# IotaWatt5_0.net
KiCad netlist of a schematic drawn in EAGLE
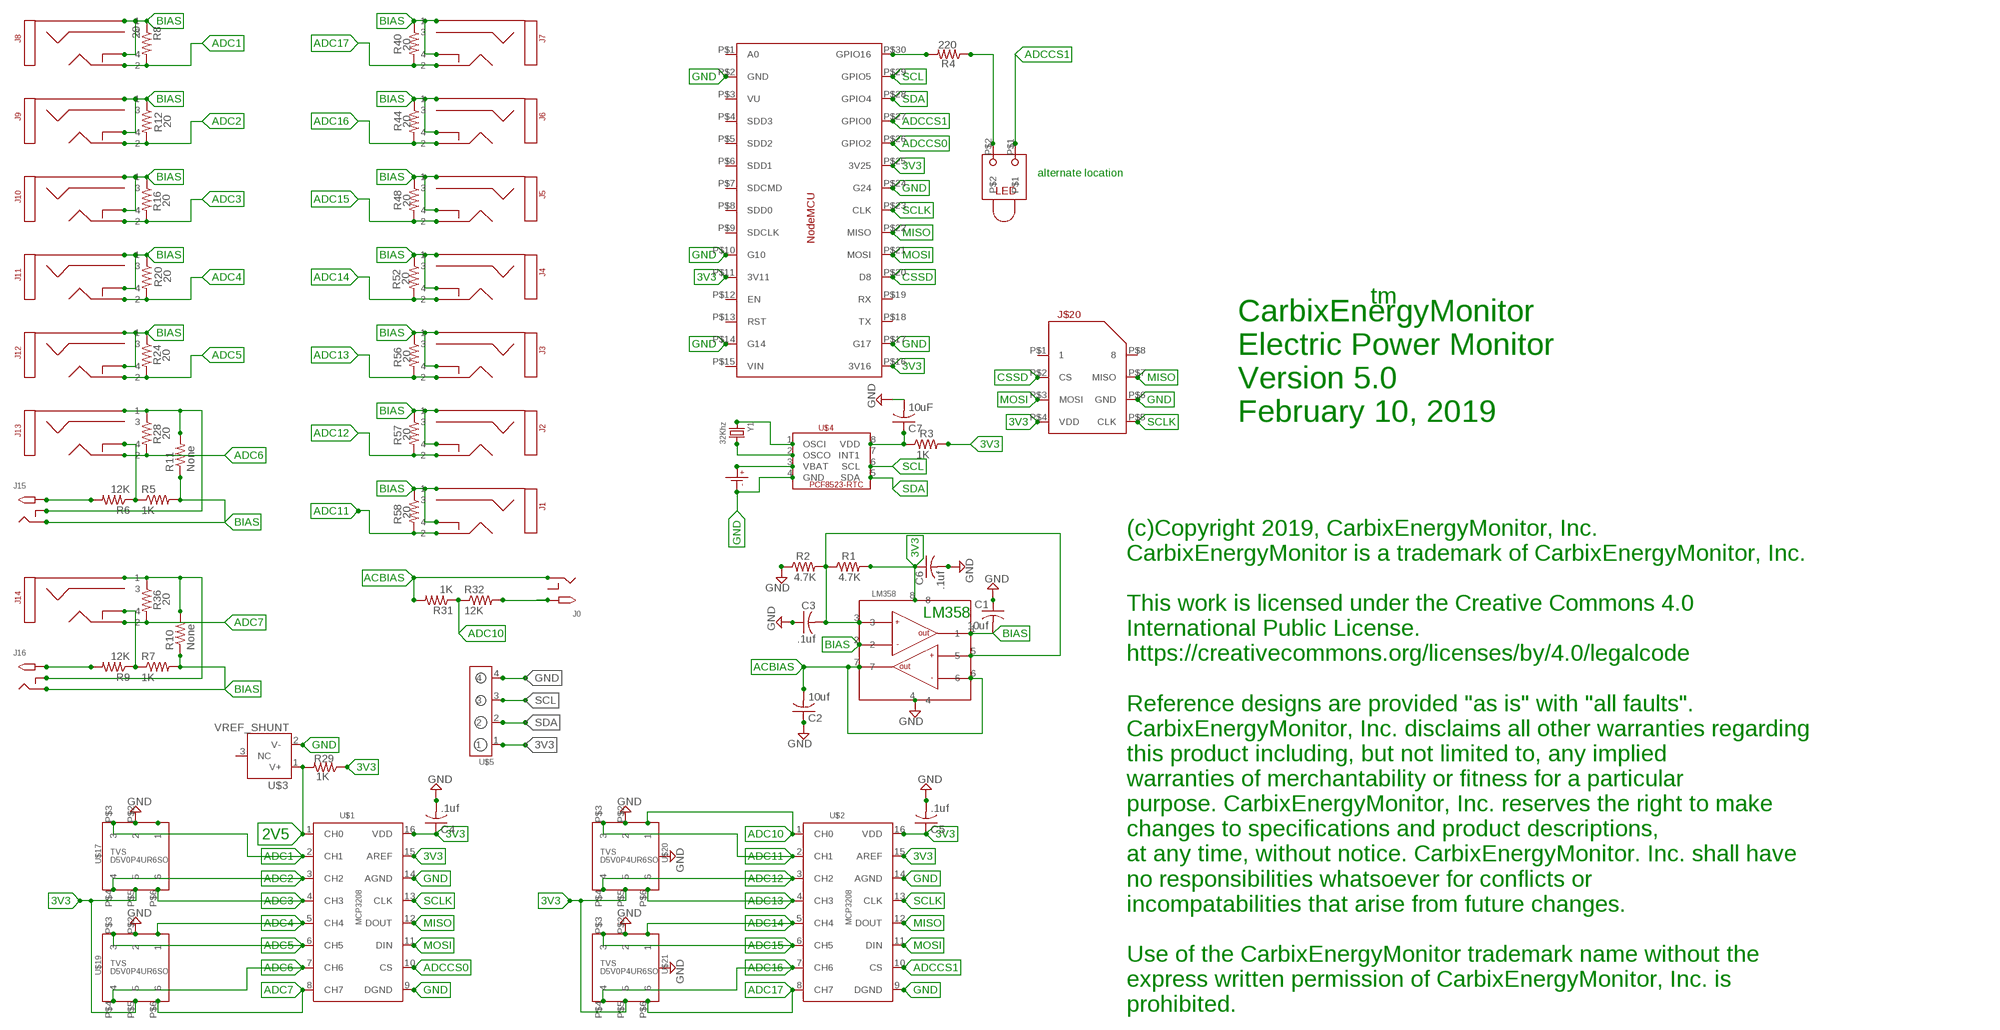
[diagram p0: schematic, sheet 1]

(export (version "E")
  (design (tool "Eeschema 10.0.6"))
  (components
    (comp (ref "C1")
      (value "10uf")
      (footprint "eagle-import:C0805")
      (libsource (lib "eagle-import") (part "C-USC0805"))
    )
    (comp (ref "C2")
      (value "10uf")
      (footprint "eagle-import:C0805")
      (libsource (lib "eagle-import") (part "C-USC0805"))
    )
    (comp (ref "C3")
      (value ".1uf")
      (footprint "eagle-import:C0805")
      (libsource (lib "eagle-import") (part "C-USC0805"))
    )
    (comp (ref "C4")
      (value ".1uf")
      (footprint "eagle-import:C0805")
      (libsource (lib "eagle-import") (part "C-USC0805"))
    )
    (comp (ref "C5")
      (value ".1uf")
      (footprint "eagle-import:C0805")
      (libsource (lib "eagle-import") (part "C-USC0805"))
    )
    (comp (ref "C6")
      (value ".1uf")
      (footprint "eagle-import:C0805")
      (libsource (lib "eagle-import") (part "C-USC0805"))
    )
    (comp (ref "C7")
      (value "10uF")
      (footprint "eagle-import:C0805")
      (libsource (lib "eagle-import") (part "C-USC0805"))
    )
    (comp (ref "J$20")
      (value "MICROSD_PUSH/PULL")
      (footprint "eagle-import:MICROSD")
      (libsource (lib "eagle-import") (part "MICROSD_PUSH/PULL"))
    )
    (comp (ref "J0")
      (value "2.1MMJACKSMT")
      (footprint "eagle-import:DCJACK_2MM_SMT")
      (libsource (lib "eagle-import") (part "2.1MMJACKSMT"))
    )
    (comp (ref "J1")
      (value "STEREO_SMD")
      (footprint "eagle-import:STEREO_SMT")
      (libsource (lib "eagle-import") (part "STEREO_SMD"))
    )
    (comp (ref "J2")
      (value "STEREO_SMD")
      (footprint "eagle-import:STEREO_SMT")
      (libsource (lib "eagle-import") (part "STEREO_SMD"))
    )
    (comp (ref "J3")
      (value "STEREO_SMD")
      (footprint "eagle-import:STEREO_SMT")
      (libsource (lib "eagle-import") (part "STEREO_SMD"))
    )
    (comp (ref "J4")
      (value "STEREO_SMD")
      (footprint "eagle-import:STEREO_SMT")
      (libsource (lib "eagle-import") (part "STEREO_SMD"))
    )
    (comp (ref "J5")
      (value "STEREO_SMD")
      (footprint "eagle-import:STEREO_SMT")
      (libsource (lib "eagle-import") (part "STEREO_SMD"))
    )
    (comp (ref "J6")
      (value "STEREO_SMD")
      (footprint "eagle-import:STEREO_SMT")
      (libsource (lib "eagle-import") (part "STEREO_SMD"))
    )
    (comp (ref "J7")
      (value "STEREO_SMD")
      (footprint "eagle-import:STEREO_SMT")
      (libsource (lib "eagle-import") (part "STEREO_SMD"))
    )
    (comp (ref "J8")
      (value "STEREO_SMD")
      (footprint "eagle-import:STEREO_SMT")
      (libsource (lib "eagle-import") (part "STEREO_SMD"))
    )
    (comp (ref "J9")
      (value "STEREO_SMD")
      (footprint "eagle-import:STEREO_SMT")
      (libsource (lib "eagle-import") (part "STEREO_SMD"))
    )
    (comp (ref "J10")
      (value "STEREO_SMD")
      (footprint "eagle-import:STEREO_SMT")
      (libsource (lib "eagle-import") (part "STEREO_SMD"))
    )
    (comp (ref "J11")
      (value "STEREO_SMD")
      (footprint "eagle-import:STEREO_SMT")
      (libsource (lib "eagle-import") (part "STEREO_SMD"))
    )
    (comp (ref "J12")
      (value "STEREO_SMD")
      (footprint "eagle-import:STEREO_SMT")
      (libsource (lib "eagle-import") (part "STEREO_SMD"))
    )
    (comp (ref "J13")
      (value "STEREO_SMD")
      (footprint "eagle-import:STEREO_SMT")
      (libsource (lib "eagle-import") (part "STEREO_SMD"))
    )
    (comp (ref "J14")
      (value "STEREO_SMD")
      (footprint "eagle-import:STEREO_SMT")
      (libsource (lib "eagle-import") (part "STEREO_SMD"))
    )
    (comp (ref "J15")
      (value "2.1MMJACKSMT")
      (footprint "eagle-import:DCJACK_2MM_SMT")
      (libsource (lib "eagle-import") (part "2.1MMJACKSMT"))
    )
    (comp (ref "J16")
      (value "2.1MMJACKSMT")
      (footprint "eagle-import:DCJACK_2MM_SMT")
      (libsource (lib "eagle-import") (part "2.1MMJACKSMT"))
    )
    (comp (ref "R1")
      (value "4.7K")
      (footprint "eagle-import:R0805")
      (libsource (lib "eagle-import") (part "R-US_R0805"))
    )
    (comp (ref "R2")
      (value "4.7K")
      (footprint "eagle-import:R0805")
      (libsource (lib "eagle-import") (part "R-US_R0805"))
    )
    (comp (ref "R3")
      (value "1K")
      (footprint "eagle-import:R0805")
      (libsource (lib "eagle-import") (part "R-US_R0805"))
    )
    (comp (ref "R4")
      (value "220")
      (footprint "eagle-import:R0805")
      (libsource (lib "eagle-import") (part "R-US_R0805"))
    )
    (comp (ref "R5")
      (value "1K")
      (footprint "eagle-import:R0805")
      (libsource (lib "eagle-import") (part "R-US_R0805"))
    )
    (comp (ref "R6")
      (value "12K")
      (footprint "eagle-import:R0805")
      (libsource (lib "eagle-import") (part "R-US_R0805"))
    )
    (comp (ref "R7")
      (value "1K")
      (footprint "eagle-import:R0805")
      (libsource (lib "eagle-import") (part "R-US_R0805"))
    )
    (comp (ref "R8")
      (value "20")
      (footprint "eagle-import:R0805")
      (libsource (lib "eagle-import") (part "R-US_R0805"))
    )
    (comp (ref "R9")
      (value "12K")
      (footprint "eagle-import:R0805")
      (libsource (lib "eagle-import") (part "R-US_R0805"))
    )
    (comp (ref "R10")
      (value "None")
      (footprint "eagle-import:R0805")
      (libsource (lib "eagle-import") (part "R-US_R0805"))
    )
    (comp (ref "R11")
      (value "None")
      (footprint "eagle-import:R0805")
      (libsource (lib "eagle-import") (part "R-US_R0805"))
    )
    (comp (ref "R12")
      (value "20")
      (footprint "eagle-import:R0805")
      (libsource (lib "eagle-import") (part "R-US_R0805"))
    )
    (comp (ref "R16")
      (value "20")
      (footprint "eagle-import:R0805")
      (libsource (lib "eagle-import") (part "R-US_R0805"))
    )
    (comp (ref "R20")
      (value "20")
      (footprint "eagle-import:R0805")
      (libsource (lib "eagle-import") (part "R-US_R0805"))
    )
    (comp (ref "R24")
      (value "20")
      (footprint "eagle-import:R0805")
      (libsource (lib "eagle-import") (part "R-US_R0805"))
    )
    (comp (ref "R28")
      (value "20")
      (footprint "eagle-import:R0805")
      (libsource (lib "eagle-import") (part "R-US_R0805"))
    )
    (comp (ref "R29")
      (value "1K")
      (footprint "eagle-import:R0805")
      (libsource (lib "eagle-import") (part "R-US_R0805"))
    )
    (comp (ref "R31")
      (value "1K")
      (footprint "eagle-import:R0805")
      (libsource (lib "eagle-import") (part "R-US_R0805"))
    )
    (comp (ref "R32")
      (value "12K")
      (footprint "eagle-import:R0805")
      (libsource (lib "eagle-import") (part "R-US_R0805"))
    )
    (comp (ref "R36")
      (value "20")
      (footprint "eagle-import:R0805")
      (libsource (lib "eagle-import") (part "R-US_R0805"))
    )
    (comp (ref "R40")
      (value "20")
      (footprint "eagle-import:R0805")
      (libsource (lib "eagle-import") (part "R-US_R0805"))
    )
    (comp (ref "R44")
      (value "20")
      (footprint "eagle-import:R0805")
      (libsource (lib "eagle-import") (part "R-US_R0805"))
    )
    (comp (ref "R48")
      (value "20")
      (footprint "eagle-import:R0805")
      (libsource (lib "eagle-import") (part "R-US_R0805"))
    )
    (comp (ref "R52")
      (value "20")
      (footprint "eagle-import:R0805")
      (libsource (lib "eagle-import") (part "R-US_R0805"))
    )
    (comp (ref "R56")
      (value "20")
      (footprint "eagle-import:R0805")
      (libsource (lib "eagle-import") (part "R-US_R0805"))
    )
    (comp (ref "R57")
      (value "20")
      (footprint "eagle-import:R0805")
      (libsource (lib "eagle-import") (part "R-US_R0805"))
    )
    (comp (ref "R58")
      (value "20")
      (footprint "eagle-import:R0805")
      (libsource (lib "eagle-import") (part "R-US_R0805"))
    )
    (comp (ref "U$1")
      (value "MCP3208")
      (footprint "eagle-import:SOIC_16")
      (libsource (lib "eagle-import") (part "MCP3208"))
    )
    (comp (ref "U$2")
      (value "MCP3208")
      (footprint "eagle-import:SOIC_16")
      (libsource (lib "eagle-import") (part "MCP3208"))
    )
    (comp (ref "U$3")
      (value "VREF_SHUNT")
      (footprint "eagle-import:SOT23_3")
      (libsource (lib "eagle-import") (part "VREF_SHUNT"))
    )
    (comp (ref "U$4")
      (value "PCF8523_RTC")
      (footprint "eagle-import:SOIC_8")
      (libsource (lib "eagle-import") (part "PCF8523_RTC"))
    )
    (comp (ref "U$5")
      (value "HEADER_1X4")
      (footprint "eagle-import:HEADER_1X4")
      (libsource (lib "eagle-import") (part "HEADER_1X4"))
    )
    (comp (ref "U$16")
      (value "NODEMCU")
      (footprint "eagle-import:NODEMCU")
      (libsource (lib "eagle-import") (part "NODEMCU"))
    )
    (comp (ref "U$17")
      (value "TVS_4CHAN_ARRAYSC-74")
      (footprint "eagle-import:SC-74")
      (libsource (lib "eagle-import") (part "TVS_4CHAN_ARRAYSC-74"))
    )
    (comp (ref "U$18")
      (value "CR1220SMD")
      (footprint "eagle-import:CR1220SMD")
      (libsource (lib "eagle-import") (part "CR1220SMD"))
    )
    (comp (ref "U$19")
      (value "TVS_4CHAN_ARRAYSC-74")
      (footprint "eagle-import:SC-74")
      (libsource (lib "eagle-import") (part "TVS_4CHAN_ARRAYSC-74"))
    )
    (comp (ref "U$20")
      (value "TVS_4CHAN_ARRAYSC-74")
      (footprint "eagle-import:SC-74")
      (libsource (lib "eagle-import") (part "TVS_4CHAN_ARRAYSC-74"))
    )
    (comp (ref "U$21")
      (value "TVS_4CHAN_ARRAYSC-74")
      (footprint "eagle-import:SC-74")
      (libsource (lib "eagle-import") (part "TVS_4CHAN_ARRAYSC-74"))
    )
    (comp (ref "U$22")
      (value "LM358_DUAL_OP-AMP")
      (footprint "eagle-import:SOIC_8")
      (libsource (lib "eagle-import") (part "LM358_DUAL_OP-AMP"))
    )
    (comp (ref "U$23")
      (value "LED_RT_TRH")
      (footprint "eagle-import:LED_TH_RT")
      (libsource (lib "eagle-import") (part "LED_RT_TRH"))
    )
    (comp (ref "Y1")
      (value "32Khz")
      (footprint "eagle-import:CRYSTAL_8X3.8")
      (libsource (lib "eagle-import") (part "CRYSTAL8X3.8SMT"))
    )
  )
  (nets
    (net (code "1") (name "2V5") (class "Default")
      (node (ref "R29") (pin "2") (pinfunction "2_2") (pintype "passive"))
      (node (ref "U$1") (pin "1") (pinfunction "CH0_1") (pintype "input"))
      (node (ref "U$3") (pin "1") (pinfunction "V+_1") (pintype "bidirectional"))
    )
    (net (code "2") (name "3V3") (class "Default")
      (node (ref "C4") (pin "1") (pinfunction "1_1") (pintype "passive"))
      (node (ref "C5") (pin "1") (pinfunction "1_1") (pintype "passive"))
      (node (ref "C6") (pin "1") (pinfunction "1_1") (pintype "passive"))
      (node (ref "J$20") (pin "P$4") (pinfunction "VDD_P$4") (pintype "bidirectional"))
      (node (ref "R1") (pin "2") (pinfunction "2_2") (pintype "passive"))
      (node (ref "R29") (pin "1") (pinfunction "1_1") (pintype "passive"))
      (node (ref "R3") (pin "2") (pinfunction "2_2") (pintype "passive"))
      (node (ref "U$1") (pin "15") (pinfunction "AREF_15") (pintype "input"))
      (node (ref "U$1") (pin "16") (pinfunction "VDD_16") (pintype "bidirectional"))
      (node (ref "U$16") (pin "P$11") (pinfunction "3V11_P$11") (pintype "bidirectional"))
      (node (ref "U$16") (pin "P$16") (pinfunction "3V16_P$16") (pintype "bidirectional"))
      (node (ref "U$16") (pin "P$25") (pinfunction "3V25_P$25") (pintype "bidirectional"))
      (node (ref "U$17") (pin "P$5") (pinfunction "5_P$5") (pintype "bidirectional"))
      (node (ref "U$19") (pin "P$5") (pinfunction "5_P$5") (pintype "bidirectional"))
      (node (ref "U$2") (pin "15") (pinfunction "AREF_15") (pintype "input"))
      (node (ref "U$2") (pin "16") (pinfunction "VDD_16") (pintype "bidirectional"))
      (node (ref "U$20") (pin "P$5") (pinfunction "5_P$5") (pintype "bidirectional"))
      (node (ref "U$21") (pin "P$5") (pinfunction "5_P$5") (pintype "bidirectional"))
      (node (ref "U$22") (pin "8") (pinfunction "8_8") (pintype "bidirectional"))
      (node (ref "U$5") (pin "1") (pinfunction "1_1") (pintype "bidirectional"))
    )
    (net (code "3") (name "ACBIAS") (class "Default")
      (node (ref "C2") (pin "2") (pinfunction "2_2") (pintype "passive"))
      (node (ref "J0") (pin "GND") (pinfunction "RING_GND") (pintype "bidirectional"))
      (node (ref "R31") (pin "2") (pinfunction "2_2") (pintype "passive"))
      (node (ref "U$22") (pin "6") (pinfunction "6_6") (pintype "bidirectional"))
      (node (ref "U$22") (pin "7") (pinfunction "7_7") (pintype "bidirectional"))
    )
    (net (code "4") (name "ADC1") (class "Default")
      (node (ref "J8") (pin "P$2") (pinfunction "2_P$2") (pintype "bidirectional"))
      (node (ref "R8") (pin "2") (pinfunction "2_2") (pintype "passive"))
      (node (ref "U$1") (pin "2") (pinfunction "CH1_2") (pintype "input"))
      (node (ref "U$17") (pin "P$3") (pinfunction "3_P$3") (pintype "bidirectional"))
    )
    (net (code "5") (name "ADC2") (class "Default")
      (node (ref "J9") (pin "P$2") (pinfunction "2_P$2") (pintype "bidirectional"))
      (node (ref "R12") (pin "2") (pinfunction "2_2") (pintype "passive"))
      (node (ref "U$1") (pin "3") (pinfunction "CH2_3") (pintype "input"))
      (node (ref "U$17") (pin "P$4") (pinfunction "4_P$4") (pintype "bidirectional"))
    )
    (net (code "6") (name "ADC3") (class "Default")
      (node (ref "J10") (pin "P$2") (pinfunction "2_P$2") (pintype "bidirectional"))
      (node (ref "R16") (pin "2") (pinfunction "2_2") (pintype "passive"))
      (node (ref "U$1") (pin "4") (pinfunction "CH3_4") (pintype "input"))
      (node (ref "U$17") (pin "P$6") (pinfunction "6_P$6") (pintype "bidirectional"))
    )
    (net (code "7") (name "ADC4") (class "Default")
      (node (ref "J11") (pin "P$2") (pinfunction "2_P$2") (pintype "bidirectional"))
      (node (ref "R20") (pin "2") (pinfunction "2_2") (pintype "passive"))
      (node (ref "U$1") (pin "5") (pinfunction "CH4_5") (pintype "bidirectional"))
      (node (ref "U$19") (pin "P$1") (pinfunction "1_P$1") (pintype "bidirectional"))
    )
    (net (code "8") (name "ADC5") (class "Default")
      (node (ref "J12") (pin "P$2") (pinfunction "2_P$2") (pintype "bidirectional"))
      (node (ref "R24") (pin "2") (pinfunction "2_2") (pintype "passive"))
      (node (ref "U$1") (pin "6") (pinfunction "CH5_6") (pintype "bidirectional"))
      (node (ref "U$19") (pin "P$3") (pinfunction "3_P$3") (pintype "bidirectional"))
    )
    (net (code "9") (name "ADC6") (class "Default")
      (node (ref "J13") (pin "P$2") (pinfunction "2_P$2") (pintype "bidirectional"))
      (node (ref "R28") (pin "2") (pinfunction "2_2") (pintype "passive"))
      (node (ref "U$1") (pin "7") (pinfunction "CH6_7") (pintype "input"))
      (node (ref "U$19") (pin "P$4") (pinfunction "4_P$4") (pintype "bidirectional"))
    )
    (net (code "10") (name "ADC7") (class "Default")
      (node (ref "J14") (pin "P$2") (pinfunction "2_P$2") (pintype "bidirectional"))
      (node (ref "R36") (pin "2") (pinfunction "2_2") (pintype "passive"))
      (node (ref "U$1") (pin "8") (pinfunction "CH7_8") (pintype "bidirectional"))
      (node (ref "U$19") (pin "P$6") (pinfunction "6_P$6") (pintype "bidirectional"))
    )
    (net (code "11") (name "ADC10") (class "Default")
      (node (ref "R31") (pin "1") (pinfunction "1_1") (pintype "passive"))
      (node (ref "R32") (pin "1") (pinfunction "1_1") (pintype "passive"))
      (node (ref "U$2") (pin "1") (pinfunction "CH0_1") (pintype "input"))
      (node (ref "U$20") (pin "P$1") (pinfunction "1_P$1") (pintype "bidirectional"))
    )
    (net (code "12") (name "ADC11") (class "Default")
      (node (ref "J1") (pin "P$2") (pinfunction "2_P$2") (pintype "bidirectional"))
      (node (ref "R58") (pin "2") (pinfunction "2_2") (pintype "passive"))
      (node (ref "U$2") (pin "2") (pinfunction "CH1_2") (pintype "input"))
      (node (ref "U$20") (pin "P$3") (pinfunction "3_P$3") (pintype "bidirectional"))
    )
    (net (code "13") (name "ADC12") (class "Default")
      (node (ref "J2") (pin "P$2") (pinfunction "2_P$2") (pintype "bidirectional"))
      (node (ref "R57") (pin "2") (pinfunction "2_2") (pintype "passive"))
      (node (ref "U$2") (pin "3") (pinfunction "CH2_3") (pintype "input"))
      (node (ref "U$20") (pin "P$4") (pinfunction "4_P$4") (pintype "bidirectional"))
    )
    (net (code "14") (name "ADC13") (class "Default")
      (node (ref "J3") (pin "P$2") (pinfunction "2_P$2") (pintype "bidirectional"))
      (node (ref "R56") (pin "2") (pinfunction "2_2") (pintype "passive"))
      (node (ref "U$2") (pin "4") (pinfunction "CH3_4") (pintype "input"))
      (node (ref "U$20") (pin "P$6") (pinfunction "6_P$6") (pintype "bidirectional"))
    )
    (net (code "15") (name "ADC14") (class "Default")
      (node (ref "J4") (pin "P$2") (pinfunction "2_P$2") (pintype "bidirectional"))
      (node (ref "R52") (pin "2") (pinfunction "2_2") (pintype "passive"))
      (node (ref "U$2") (pin "5") (pinfunction "CH4_5") (pintype "bidirectional"))
      (node (ref "U$21") (pin "P$1") (pinfunction "1_P$1") (pintype "bidirectional"))
    )
    (net (code "16") (name "ADC15") (class "Default")
      (node (ref "J5") (pin "P$2") (pinfunction "2_P$2") (pintype "bidirectional"))
      (node (ref "R48") (pin "2") (pinfunction "2_2") (pintype "passive"))
      (node (ref "U$2") (pin "6") (pinfunction "CH5_6") (pintype "bidirectional"))
      (node (ref "U$21") (pin "P$3") (pinfunction "3_P$3") (pintype "bidirectional"))
    )
    (net (code "17") (name "ADC16") (class "Default")
      (node (ref "J6") (pin "P$2") (pinfunction "2_P$2") (pintype "bidirectional"))
      (node (ref "R44") (pin "2") (pinfunction "2_2") (pintype "passive"))
      (node (ref "U$2") (pin "7") (pinfunction "CH6_7") (pintype "input"))
      (node (ref "U$21") (pin "P$4") (pinfunction "4_P$4") (pintype "bidirectional"))
    )
    (net (code "18") (name "ADC17") (class "Default")
      (node (ref "J7") (pin "P$2") (pinfunction "2_P$2") (pintype "bidirectional"))
      (node (ref "R40") (pin "2") (pinfunction "2_2") (pintype "passive"))
      (node (ref "U$2") (pin "8") (pinfunction "CH7_8") (pintype "bidirectional"))
      (node (ref "U$21") (pin "P$6") (pinfunction "6_P$6") (pintype "bidirectional"))
    )
    (net (code "19") (name "ADCCS0") (class "Default")
      (node (ref "U$1") (pin "10") (pinfunction "CS_10") (pintype "input"))
      (node (ref "U$16") (pin "P$26") (pinfunction "GPIO2_P$26") (pintype "bidirectional"))
    )
    (net (code "20") (name "ADCCS1") (class "Default")
      (node (ref "U$16") (pin "P$27") (pinfunction "GPIO0_P$27") (pintype "bidirectional"))
      (node (ref "U$2") (pin "10") (pinfunction "CS_10") (pintype "input"))
      (node (ref "U$23") (pin "P$1") (pinfunction "P$1_P$1") (pintype "bidirectional"))
    )
    (net (code "21") (name "BIAS") (class "Default")
      (node (ref "C1") (pin "2") (pinfunction "2_2") (pintype "passive"))
      (node (ref "J1") (pin "P$1") (pinfunction "1_P$1") (pintype "bidirectional"))
      (node (ref "J1") (pin "P$4") (pinfunction "4_P$4") (pintype "bidirectional"))
      (node (ref "J10") (pin "P$1") (pinfunction "1_P$1") (pintype "bidirectional"))
      (node (ref "J10") (pin "P$4") (pinfunction "4_P$4") (pintype "bidirectional"))
      (node (ref "J11") (pin "P$1") (pinfunction "1_P$1") (pintype "bidirectional"))
      (node (ref "J11") (pin "P$4") (pinfunction "4_P$4") (pintype "bidirectional"))
      (node (ref "J12") (pin "P$1") (pinfunction "1_P$1") (pintype "bidirectional"))
      (node (ref "J12") (pin "P$4") (pinfunction "4_P$4") (pintype "bidirectional"))
      (node (ref "J15") (pin "GND") (pinfunction "RING_GND") (pintype "bidirectional"))
      (node (ref "J16") (pin "GND") (pinfunction "RING_GND") (pintype "bidirectional"))
      (node (ref "J2") (pin "P$1") (pinfunction "1_P$1") (pintype "bidirectional"))
      (node (ref "J2") (pin "P$4") (pinfunction "4_P$4") (pintype "bidirectional"))
      (node (ref "J3") (pin "P$1") (pinfunction "1_P$1") (pintype "bidirectional"))
      (node (ref "J3") (pin "P$4") (pinfunction "4_P$4") (pintype "bidirectional"))
      (node (ref "J4") (pin "P$1") (pinfunction "1_P$1") (pintype "bidirectional"))
      (node (ref "J4") (pin "P$4") (pinfunction "4_P$4") (pintype "bidirectional"))
      (node (ref "J5") (pin "P$1") (pinfunction "1_P$1") (pintype "bidirectional"))
      (node (ref "J5") (pin "P$4") (pinfunction "4_P$4") (pintype "bidirectional"))
      (node (ref "J6") (pin "P$1") (pinfunction "1_P$1") (pintype "bidirectional"))
      (node (ref "J6") (pin "P$4") (pinfunction "4_P$4") (pintype "bidirectional"))
      (node (ref "J7") (pin "P$1") (pinfunction "1_P$1") (pintype "bidirectional"))
      (node (ref "J7") (pin "P$4") (pinfunction "4_P$4") (pintype "bidirectional"))
      (node (ref "J8") (pin "P$1") (pinfunction "1_P$1") (pintype "bidirectional"))
      (node (ref "J8") (pin "P$4") (pinfunction "4_P$4") (pintype "bidirectional"))
      (node (ref "J9") (pin "P$1") (pinfunction "1_P$1") (pintype "bidirectional"))
      (node (ref "J9") (pin "P$4") (pinfunction "4_P$4") (pintype "bidirectional"))
      (node (ref "R10") (pin "1") (pinfunction "1_1") (pintype "passive"))
      (node (ref "R11") (pin "1") (pinfunction "1_1") (pintype "passive"))
      (node (ref "R12") (pin "1") (pinfunction "1_1") (pintype "passive"))
      (node (ref "R16") (pin "1") (pinfunction "1_1") (pintype "passive"))
      (node (ref "R20") (pin "1") (pinfunction "1_1") (pintype "passive"))
      (node (ref "R24") (pin "1") (pinfunction "1_1") (pintype "passive"))
      (node (ref "R40") (pin "1") (pinfunction "1_1") (pintype "passive"))
      (node (ref "R44") (pin "1") (pinfunction "1_1") (pintype "passive"))
      (node (ref "R48") (pin "1") (pinfunction "1_1") (pintype "passive"))
      (node (ref "R5") (pin "2") (pinfunction "2_2") (pintype "passive"))
      (node (ref "R52") (pin "1") (pinfunction "1_1") (pintype "passive"))
      (node (ref "R56") (pin "1") (pinfunction "1_1") (pintype "passive"))
      (node (ref "R57") (pin "1") (pinfunction "1_1") (pintype "passive"))
      (node (ref "R58") (pin "1") (pinfunction "1_1") (pintype "passive"))
      (node (ref "R7") (pin "2") (pinfunction "2_2") (pintype "passive"))
      (node (ref "R8") (pin "1") (pinfunction "1_1") (pintype "passive"))
      (node (ref "U$22") (pin "1") (pinfunction "1_1") (pintype "bidirectional"))
      (node (ref "U$22") (pin "2") (pinfunction "2_2") (pintype "bidirectional"))
    )
    (net (code "22") (name "CSSD") (class "Default")
      (node (ref "J$20") (pin "P$2") (pinfunction "CS_P$2") (pintype "bidirectional"))
      (node (ref "U$16") (pin "P$20") (pinfunction "D8_P$20") (pintype "bidirectional"))
    )
    (net (code "23") (name "GND") (class "Default")
      (node (ref "C1") (pin "1") (pinfunction "1_1") (pintype "passive"))
      (node (ref "C2") (pin "1") (pinfunction "1_1") (pintype "passive"))
      (node (ref "C3") (pin "1") (pinfunction "1_1") (pintype "passive"))
      (node (ref "C4") (pin "2") (pinfunction "2_2") (pintype "passive"))
      (node (ref "C5") (pin "2") (pinfunction "2_2") (pintype "passive"))
      (node (ref "C6") (pin "2") (pinfunction "2_2") (pintype "passive"))
      (node (ref "C7") (pin "2") (pinfunction "2_2") (pintype "passive"))
      (node (ref "J$20") (pin "P$6") (pinfunction "GND_P$6") (pintype "bidirectional"))
      (node (ref "R2") (pin "1") (pinfunction "1_1") (pintype "passive"))
      (node (ref "U$1") (pin "14") (pinfunction "AGND_14") (pintype "input"))
      (node (ref "U$1") (pin "9") (pinfunction "DGND_9") (pintype "bidirectional"))
      (node (ref "U$16") (pin "P$10") (pinfunction "G10_P$10") (pintype "bidirectional"))
      (node (ref "U$16") (pin "P$14") (pinfunction "G14_P$14") (pintype "bidirectional"))
      (node (ref "U$16") (pin "P$17") (pinfunction "G17_P$17") (pintype "bidirectional"))
      (node (ref "U$16") (pin "P$2") (pinfunction "GND_P$2") (pintype "bidirectional"))
      (node (ref "U$16") (pin "P$24") (pinfunction "G24_P$24") (pintype "bidirectional"))
      (node (ref "U$17") (pin "P$2") (pinfunction "2_P$2") (pintype "bidirectional"))
      (node (ref "U$18") (pin "P-") (pinfunction "P$-_P-") (pintype "bidirectional"))
      (node (ref "U$19") (pin "P$2") (pinfunction "2_P$2") (pintype "bidirectional"))
      (node (ref "U$2") (pin "14") (pinfunction "AGND_14") (pintype "input"))
      (node (ref "U$2") (pin "9") (pinfunction "DGND_9") (pintype "bidirectional"))
      (node (ref "U$20") (pin "P$2") (pinfunction "2_P$2") (pintype "bidirectional"))
      (node (ref "U$21") (pin "P$2") (pinfunction "2_P$2") (pintype "bidirectional"))
      (node (ref "U$22") (pin "4") (pinfunction "4_4") (pintype "bidirectional"))
      (node (ref "U$3") (pin "2") (pinfunction "V-_2") (pintype "bidirectional"))
      (node (ref "U$4") (pin "4") (pinfunction "GND_4") (pintype "bidirectional"))
      (node (ref "U$5") (pin "4") (pinfunction "4_4") (pintype "bidirectional"))
    )
    (net (code "24") (name "MISO") (class "Default")
      (node (ref "J$20") (pin "P$7") (pinfunction "MISO_P$7") (pintype "bidirectional"))
      (node (ref "U$1") (pin "12") (pinfunction "DOUT_12") (pintype "bidirectional"))
      (node (ref "U$16") (pin "P$22") (pinfunction "MISO_P$22") (pintype "bidirectional"))
      (node (ref "U$2") (pin "12") (pinfunction "DOUT_12") (pintype "bidirectional"))
    )
    (net (code "25") (name "MOSI") (class "Default")
      (node (ref "J$20") (pin "P$3") (pinfunction "MOSI_P$3") (pintype "bidirectional"))
      (node (ref "U$1") (pin "11") (pinfunction "DIN_11") (pintype "input"))
      (node (ref "U$16") (pin "P$21") (pinfunction "MOSI_P$21") (pintype "bidirectional"))
      (node (ref "U$2") (pin "11") (pinfunction "DIN_11") (pintype "input"))
    )
    (net (code "26") (name "Net-(C3-Pad2)") (class "Default")
      (node (ref "C3") (pin "2") (pinfunction "2_2") (pintype "passive"))
      (node (ref "R1") (pin "1") (pinfunction "1_1") (pintype "passive"))
      (node (ref "R2") (pin "2") (pinfunction "2_2") (pintype "passive"))
      (node (ref "U$22") (pin "3") (pinfunction "3_3") (pintype "bidirectional"))
      (node (ref "U$22") (pin "5") (pinfunction "5_5") (pintype "bidirectional"))
    )
    (net (code "27") (name "Net-(J0-TIP)") (class "Default")
      (node (ref "J0") (pin "PWR2") (pinfunction "TIP_PWR2") (pintype "bidirectional"))
      (node (ref "R32") (pin "2") (pinfunction "2_2") (pintype "passive"))
    )
    (net (code "28") (name "Net-(J13-1)") (class "Default")
      (node (ref "J13") (pin "P$1") (pinfunction "1_P$1") (pintype "bidirectional"))
      (node (ref "J15") (pin "GNDBREAK") (pinfunction "RING_SW_GNDBREAK") (pintype "bidirectional"))
      (node (ref "R11") (pin "2") (pinfunction "2_2") (pintype "passive"))
      (node (ref "R28") (pin "1") (pinfunction "1_1") (pintype "passive"))
    )
    (net (code "29") (name "Net-(J13-4)") (class "Default")
      (node (ref "J13") (pin "P$4") (pinfunction "4_P$4") (pintype "bidirectional"))
      (node (ref "R5") (pin "1") (pinfunction "1_1") (pintype "passive"))
      (node (ref "R6") (pin "1") (pinfunction "1_1") (pintype "passive"))
    )
    (net (code "30") (name "Net-(J14-1)") (class "Default")
      (node (ref "J14") (pin "P$1") (pinfunction "1_P$1") (pintype "bidirectional"))
      (node (ref "J16") (pin "GNDBREAK") (pinfunction "RING_SW_GNDBREAK") (pintype "bidirectional"))
      (node (ref "R10") (pin "2") (pinfunction "2_2") (pintype "passive"))
      (node (ref "R36") (pin "1") (pinfunction "1_1") (pintype "passive"))
    )
    (net (code "31") (name "Net-(J14-4)") (class "Default")
      (node (ref "J14") (pin "P$4") (pinfunction "4_P$4") (pintype "bidirectional"))
      (node (ref "R7") (pin "1") (pinfunction "1_1") (pintype "passive"))
      (node (ref "R9") (pin "1") (pinfunction "1_1") (pintype "passive"))
    )
    (net (code "32") (name "Net-(J15-TIP)") (class "Default")
      (node (ref "J15") (pin "PWR2") (pinfunction "TIP_PWR2") (pintype "bidirectional"))
      (node (ref "R6") (pin "2") (pinfunction "2_2") (pintype "passive"))
    )
    (net (code "33") (name "Net-(J16-TIP)") (class "Default")
      (node (ref "J16") (pin "PWR2") (pinfunction "TIP_PWR2") (pintype "bidirectional"))
      (node (ref "R9") (pin "2") (pinfunction "2_2") (pintype "passive"))
    )
    (net (code "34") (name "Net-(R4-Pad1)") (class "Default")
      (node (ref "R4") (pin "1") (pinfunction "1_1") (pintype "passive"))
      (node (ref "U$23") (pin "P$2") (pinfunction "P$2_P$2") (pintype "bidirectional"))
    )
    (net (code "35") (name "Net-(U$4-OSCI)") (class "Default")
      (node (ref "U$4") (pin "1") (pinfunction "OSCI_1") (pintype "bidirectional"))
      (node (ref "Y1") (pin "P$1") (pinfunction "1_P$1") (pintype "passive"))
    )
    (net (code "36") (name "Net-(U$4-OSCO)") (class "Default")
      (node (ref "U$4") (pin "2") (pinfunction "OSCO_2") (pintype "bidirectional"))
      (node (ref "Y1") (pin "P$4") (pinfunction "2_P$4") (pintype "passive"))
    )
    (net (code "37") (name "Net-(U$4-VDD)") (class "Default")
      (node (ref "C7") (pin "1") (pinfunction "1_1") (pintype "passive"))
      (node (ref "R3") (pin "1") (pinfunction "1_1") (pintype "passive"))
      (node (ref "U$4") (pin "8") (pinfunction "VDD_8") (pintype "bidirectional"))
    )
    (net (code "38") (name "Net-(U$16-GPIO16)") (class "Default")
      (node (ref "R4") (pin "2") (pinfunction "2_2") (pintype "passive"))
      (node (ref "U$16") (pin "P$30") (pinfunction "GPIO16_P$30") (pintype "bidirectional"))
    )
    (net (code "39") (name "Net-(U$18-P$+)") (class "Default")
      (node (ref "U$18") (pin "P+") (pinfunction "P$+_P+") (pintype "bidirectional"))
      (node (ref "U$4") (pin "3") (pinfunction "VBAT_3") (pintype "bidirectional"))
    )
    (net (code "40") (name "SCL") (class "Default")
      (node (ref "U$16") (pin "P$29") (pinfunction "GPIO5_P$29") (pintype "bidirectional"))
      (node (ref "U$4") (pin "6") (pinfunction "SCL_6") (pintype "bidirectional"))
      (node (ref "U$5") (pin "3") (pinfunction "3_3") (pintype "bidirectional"))
    )
    (net (code "41") (name "SCLK") (class "Default")
      (node (ref "J$20") (pin "P$5") (pinfunction "CLK_P$5") (pintype "bidirectional"))
      (node (ref "U$1") (pin "13") (pinfunction "CLK_13") (pintype "input"))
      (node (ref "U$16") (pin "P$23") (pinfunction "CLK_P$23") (pintype "bidirectional"))
      (node (ref "U$2") (pin "13") (pinfunction "CLK_13") (pintype "input"))
    )
    (net (code "42") (name "SDA") (class "Default")
      (node (ref "U$16") (pin "P$28") (pinfunction "GPIO4_P$28") (pintype "bidirectional"))
      (node (ref "U$4") (pin "5") (pinfunction "SDA_5") (pintype "bidirectional"))
      (node (ref "U$5") (pin "2") (pinfunction "2_2") (pintype "bidirectional"))
    )
    (net (code "43") (name "unconnected-(J$20-1-PadP$1)") (class "Default")
      (node (ref "J$20") (pin "P$1") (pinfunction "1_P$1") (pintype "bidirectional"))
    )
    (net (code "44") (name "unconnected-(J$20-8-PadP$8)") (class "Default")
      (node (ref "J$20") (pin "P$8") (pinfunction "8_P$8") (pintype "bidirectional"))
    )
    (net (code "45") (name "unconnected-(J0-RING_SW-PadGNDBREAK)") (class "Default")
      (node (ref "J0") (pin "GNDBREAK") (pinfunction "RING_SW_GNDBREAK") (pintype "bidirectional"))
    )
    (net (code "46") (name "unconnected-(J1-3-PadP$3)") (class "Default")
      (node (ref "J1") (pin "P$3") (pinfunction "3_P$3") (pintype "bidirectional"))
    )
    (net (code "47") (name "unconnected-(J2-3-PadP$3)") (class "Default")
      (node (ref "J2") (pin "P$3") (pinfunction "3_P$3") (pintype "bidirectional"))
    )
    (net (code "48") (name "unconnected-(J3-3-PadP$3)") (class "Default")
      (node (ref "J3") (pin "P$3") (pinfunction "3_P$3") (pintype "bidirectional"))
    )
    (net (code "49") (name "unconnected-(J4-3-PadP$3)") (class "Default")
      (node (ref "J4") (pin "P$3") (pinfunction "3_P$3") (pintype "bidirectional"))
    )
    (net (code "50") (name "unconnected-(J5-3-PadP$3)") (class "Default")
      (node (ref "J5") (pin "P$3") (pinfunction "3_P$3") (pintype "bidirectional"))
    )
    (net (code "51") (name "unconnected-(J6-3-PadP$3)") (class "Default")
      (node (ref "J6") (pin "P$3") (pinfunction "3_P$3") (pintype "bidirectional"))
    )
    (net (code "52") (name "unconnected-(J7-3-PadP$3)") (class "Default")
      (node (ref "J7") (pin "P$3") (pinfunction "3_P$3") (pintype "bidirectional"))
    )
    (net (code "53") (name "unconnected-(J8-3-PadP$3)") (class "Default")
      (node (ref "J8") (pin "P$3") (pinfunction "3_P$3") (pintype "bidirectional"))
    )
    (net (code "54") (name "unconnected-(J9-3-PadP$3)") (class "Default")
      (node (ref "J9") (pin "P$3") (pinfunction "3_P$3") (pintype "bidirectional"))
    )
    (net (code "55") (name "unconnected-(J10-3-PadP$3)") (class "Default")
      (node (ref "J10") (pin "P$3") (pinfunction "3_P$3") (pintype "bidirectional"))
    )
    (net (code "56") (name "unconnected-(J11-3-PadP$3)") (class "Default")
      (node (ref "J11") (pin "P$3") (pinfunction "3_P$3") (pintype "bidirectional"))
    )
    (net (code "57") (name "unconnected-(J12-3-PadP$3)") (class "Default")
      (node (ref "J12") (pin "P$3") (pinfunction "3_P$3") (pintype "bidirectional"))
    )
    (net (code "58") (name "unconnected-(J13-3-PadP$3)") (class "Default")
      (node (ref "J13") (pin "P$3") (pinfunction "3_P$3") (pintype "bidirectional"))
    )
    (net (code "59") (name "unconnected-(J14-3-PadP$3)") (class "Default")
      (node (ref "J14") (pin "P$3") (pinfunction "3_P$3") (pintype "bidirectional"))
    )
    (net (code "60") (name "unconnected-(U$3-NC-Pad3)") (class "Default")
      (node (ref "U$3") (pin "3") (pinfunction "NC_3") (pintype "bidirectional"))
    )
    (net (code "61") (name "unconnected-(U$4-INT1-Pad7)") (class "Default")
      (node (ref "U$4") (pin "7") (pinfunction "INT1_7") (pintype "bidirectional"))
    )
    (net (code "62") (name "unconnected-(U$16-A0-PadP$1)") (class "Default")
      (node (ref "U$16") (pin "P$1") (pinfunction "A0_P$1") (pintype "bidirectional"))
    )
    (net (code "63") (name "unconnected-(U$16-EN-PadP$12)") (class "Default")
      (node (ref "U$16") (pin "P$12") (pinfunction "EN_P$12") (pintype "bidirectional"))
    )
    (net (code "64") (name "unconnected-(U$16-RST-PadP$13)") (class "Default")
      (node (ref "U$16") (pin "P$13") (pinfunction "RST_P$13") (pintype "bidirectional"))
    )
    (net (code "65") (name "unconnected-(U$16-RX-PadP$19)") (class "Default")
      (node (ref "U$16") (pin "P$19") (pinfunction "RX_P$19") (pintype "bidirectional"))
    )
    (net (code "66") (name "unconnected-(U$16-SDCLK-PadP$9)") (class "Default")
      (node (ref "U$16") (pin "P$9") (pinfunction "SDCLK_P$9") (pintype "bidirectional"))
    )
    (net (code "67") (name "unconnected-(U$16-SDCMD-PadP$7)") (class "Default")
      (node (ref "U$16") (pin "P$7") (pinfunction "SDCMD_P$7") (pintype "bidirectional"))
    )
    (net (code "68") (name "unconnected-(U$16-SDD0-PadP$8)") (class "Default")
      (node (ref "U$16") (pin "P$8") (pinfunction "SDD0_P$8") (pintype "bidirectional"))
    )
    (net (code "69") (name "unconnected-(U$16-SDD1-PadP$6)") (class "Default")
      (node (ref "U$16") (pin "P$6") (pinfunction "SDD1_P$6") (pintype "bidirectional"))
    )
    (net (code "70") (name "unconnected-(U$16-SDD2-PadP$5)") (class "Default")
      (node (ref "U$16") (pin "P$5") (pinfunction "SDD2_P$5") (pintype "bidirectional"))
    )
    (net (code "71") (name "unconnected-(U$16-SDD3-PadP$4)") (class "Default")
      (node (ref "U$16") (pin "P$4") (pinfunction "SDD3_P$4") (pintype "bidirectional"))
    )
    (net (code "72") (name "unconnected-(U$16-TX-PadP$18)") (class "Default")
      (node (ref "U$16") (pin "P$18") (pinfunction "TX_P$18") (pintype "bidirectional"))
    )
    (net (code "73") (name "unconnected-(U$16-VIN-PadP$15)") (class "Default")
      (node (ref "U$16") (pin "P$15") (pinfunction "VIN_P$15") (pintype "bidirectional"))
    )
    (net (code "74") (name "unconnected-(U$16-VU-PadP$3)") (class "Default")
      (node (ref "U$16") (pin "P$3") (pinfunction "VU_P$3") (pintype "bidirectional"))
    )
    (net (code "75") (name "unconnected-(U$17-1-PadP$1)") (class "Default")
      (node (ref "U$17") (pin "P$1") (pinfunction "1_P$1") (pintype "bidirectional"))
    )
  )
)
